# Sheet1.net
KiCad netlist of a schematic drawn in Altium Designer
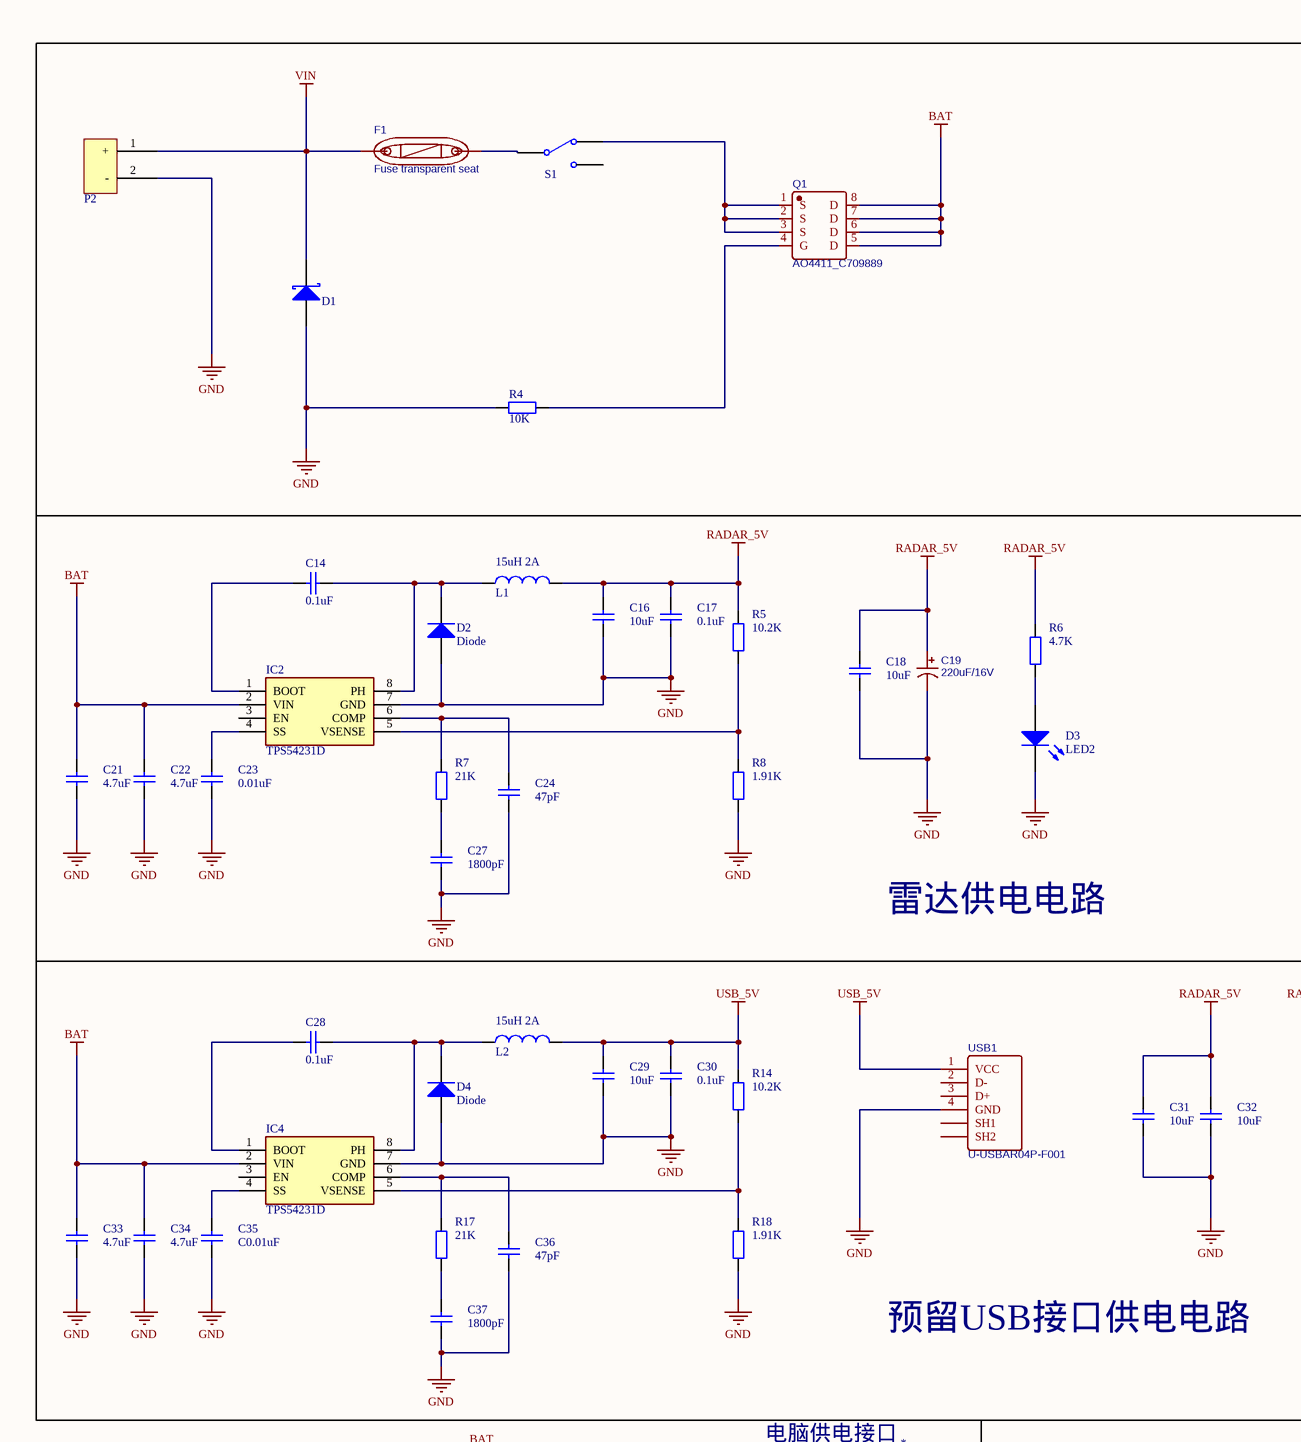
[diagram p0: Sheet1.SchDoc, top left]
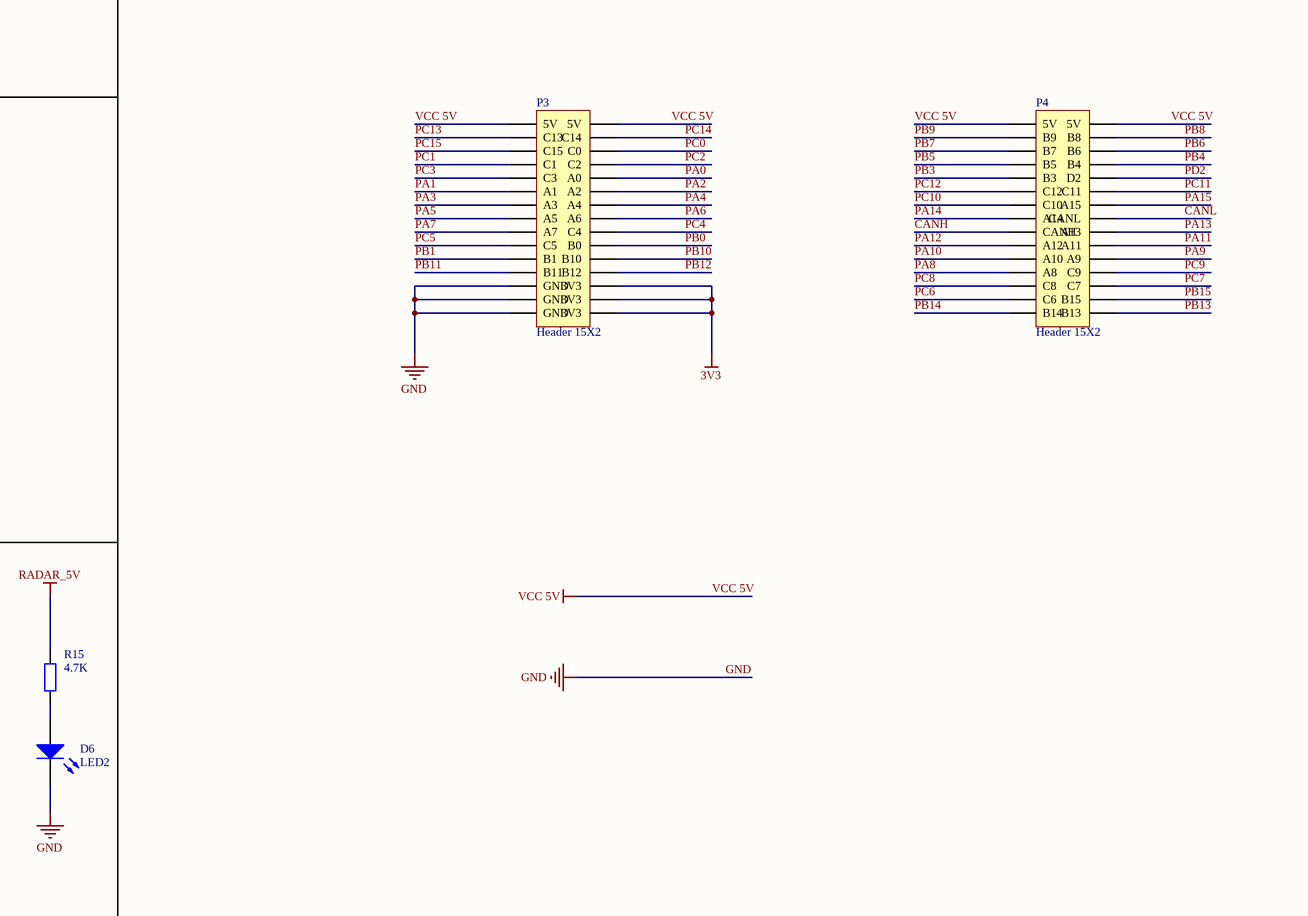
[diagram p1: Sheet1.SchDoc, top middle]
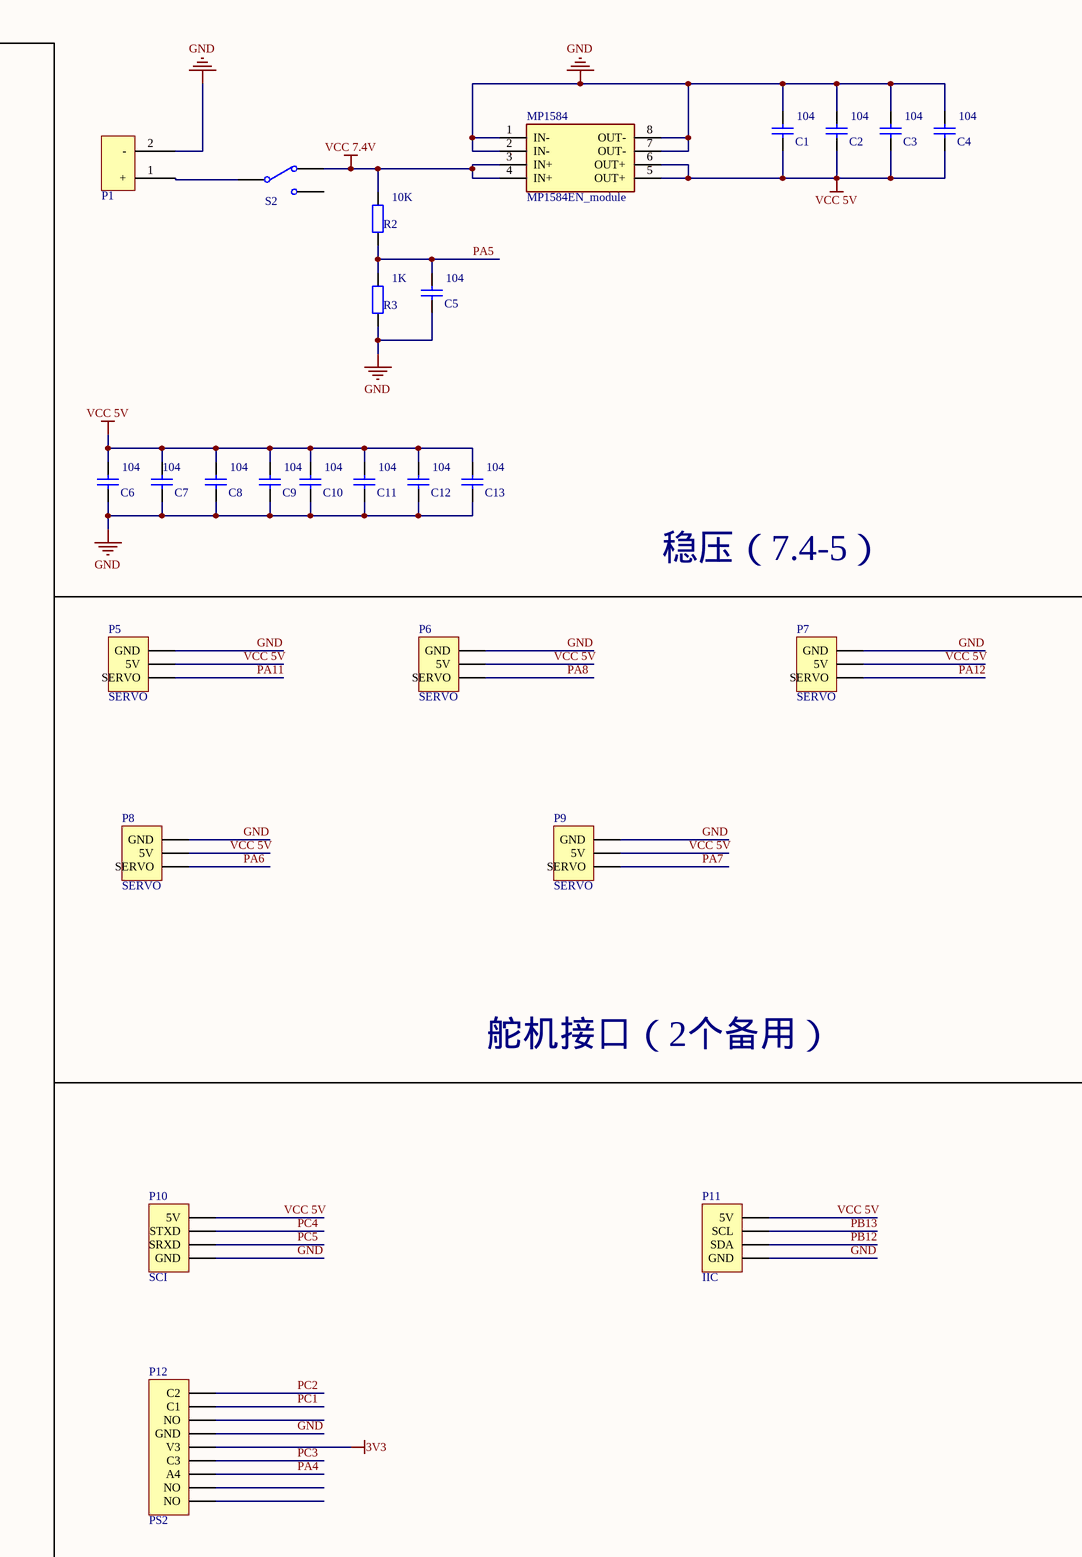
[diagram p2: Sheet1.SchDoc, top right]
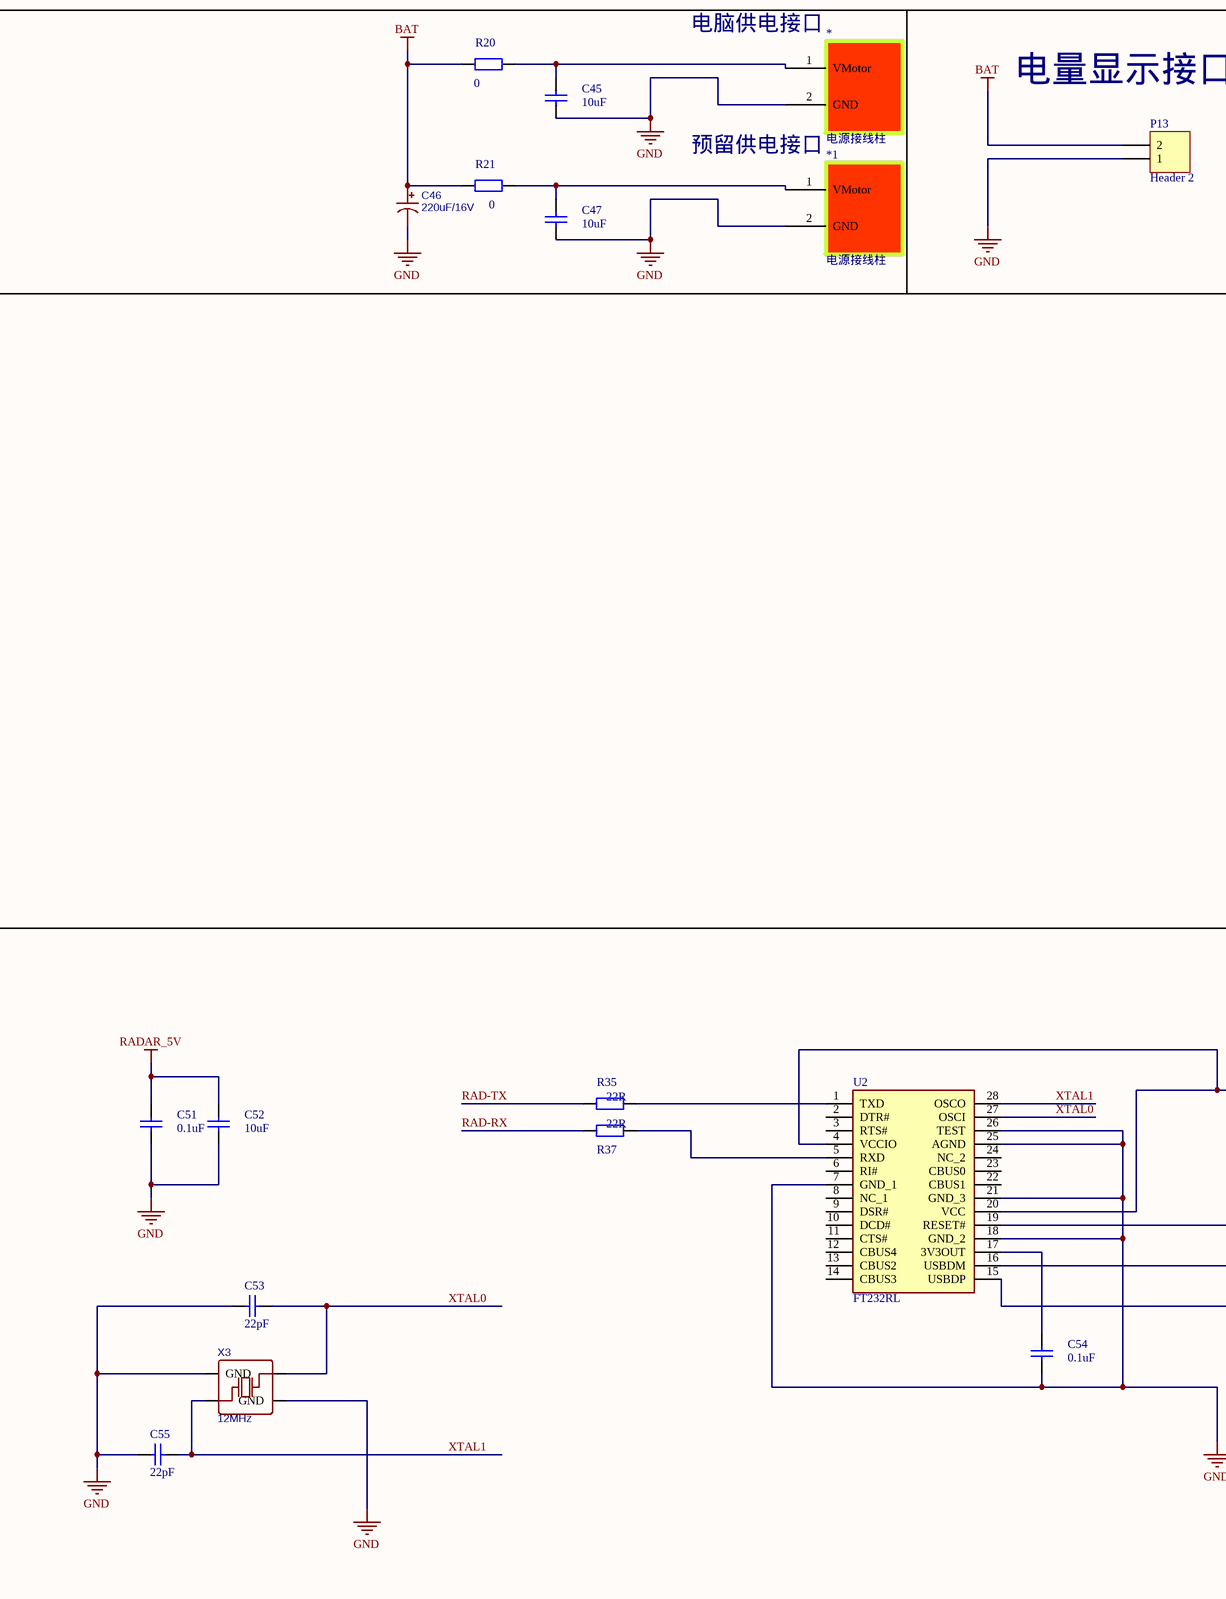
[diagram p3: Sheet1.SchDoc, bottom left]
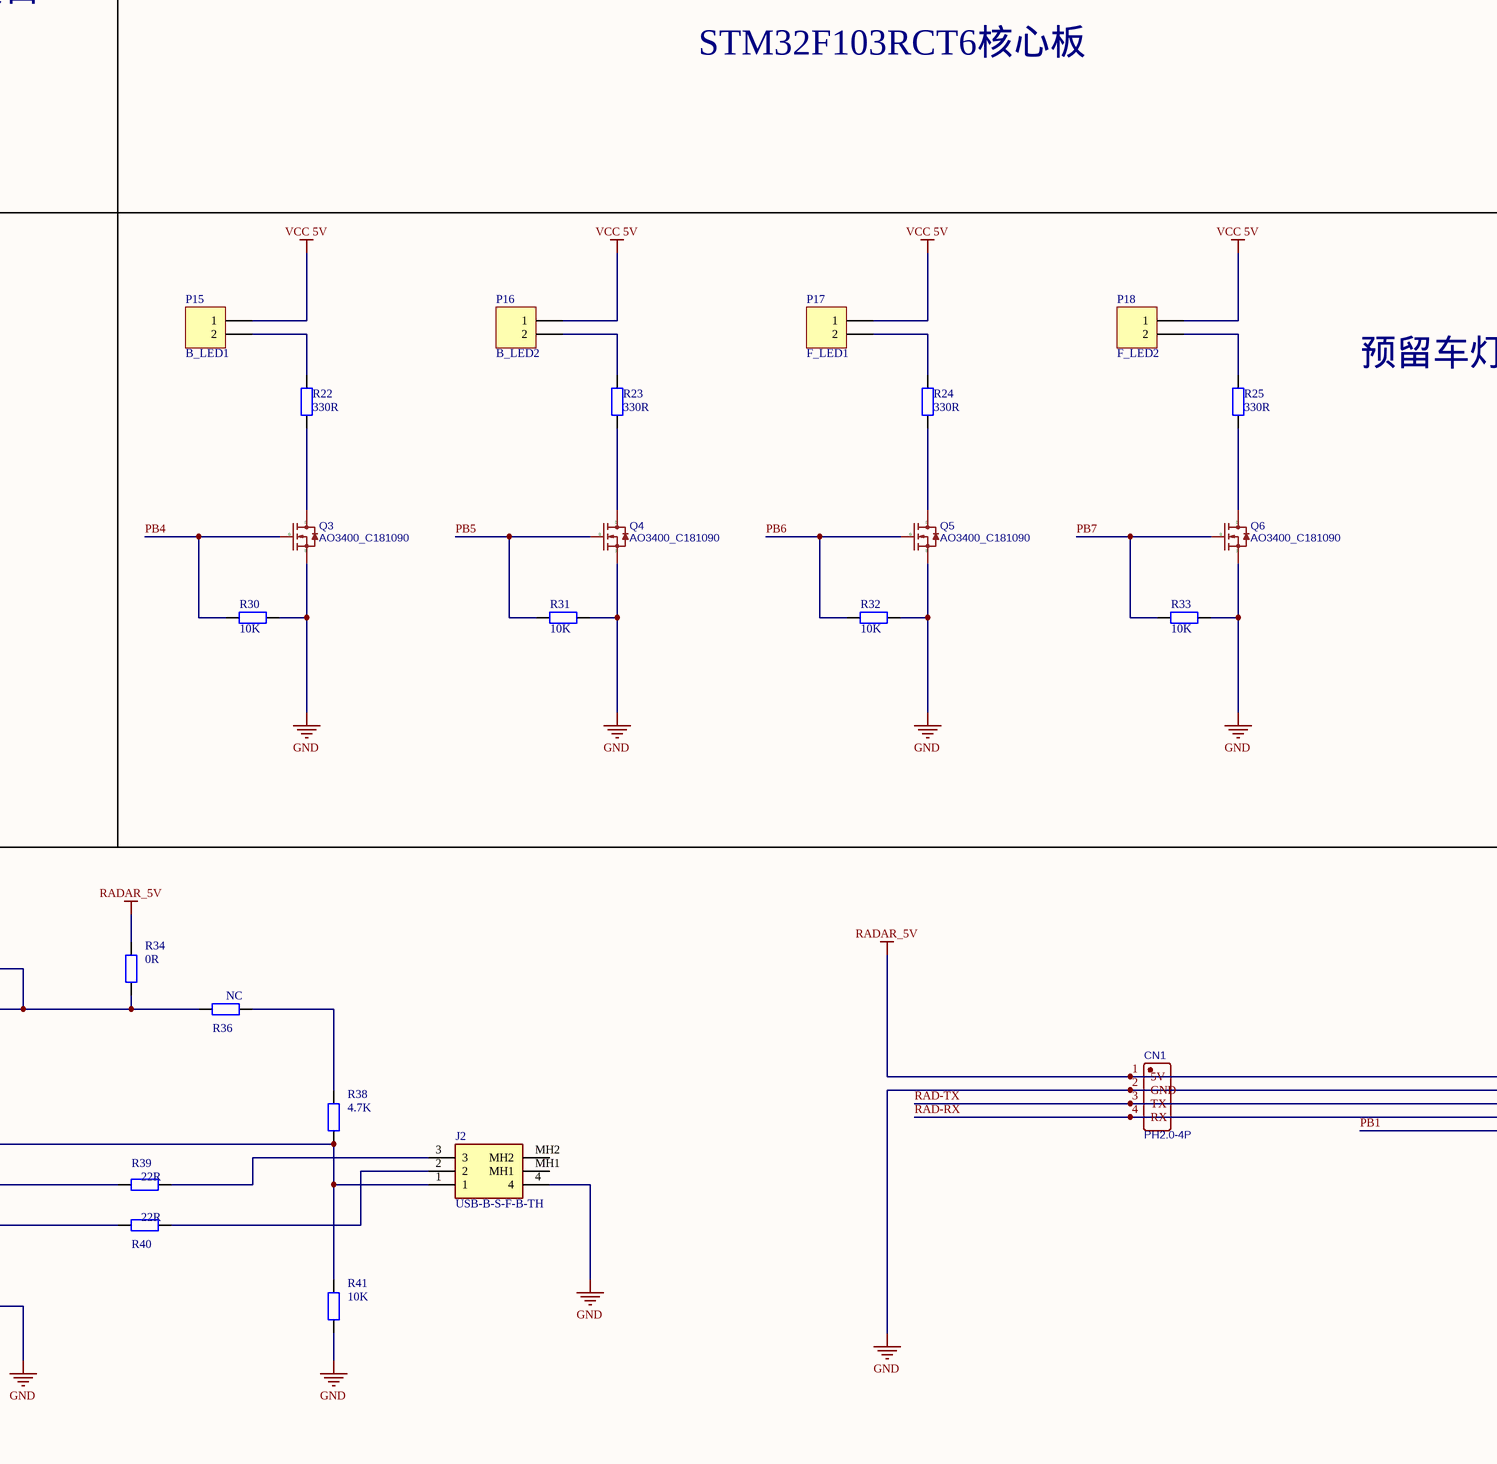
[diagram p4: Sheet1.SchDoc, bottom middle]
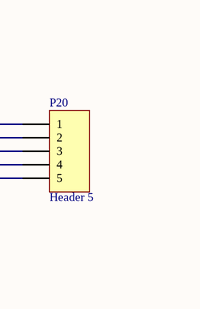
[diagram p5: Sheet1.SchDoc, bottom right]

(export (version "E")
  (design (tool "Eeschema 10.0.6"))
  (components
    (comp (ref "*") (value "电源接线柱") (footprint "接线柱") (libsource (lib "智能车元件") (part "电源接线柱")))
    (comp (ref "*1") (value "电源接线柱") (footprint "接线柱") (libsource (lib "智能车元件") (part "电源接线柱")))
    (comp (ref "C1")
      (value "104")
      (footprint "0805")
      (fields (field (name "PUBLISHER") "Altium Limited"))
      (libsource (lib "智能车元件") (part "C"))
    )
    (comp (ref "C2")
      (value "104")
      (footprint "0805")
      (fields (field (name "PUBLISHER") "Altium Limited"))
      (libsource (lib "智能车元件") (part "C"))
    )
    (comp (ref "C3")
      (value "104")
      (footprint "0805")
      (fields (field (name "PUBLISHER") "Altium Limited"))
      (libsource (lib "智能车元件") (part "C"))
    )
    (comp (ref "C4")
      (value "104")
      (footprint "0805")
      (fields (field (name "PUBLISHER") "Altium Limited"))
      (libsource (lib "智能车元件") (part "C"))
    )
    (comp (ref "C5")
      (value "104")
      (footprint "0805")
      (fields (field (name "PUBLISHER") "Altium Limited"))
      (libsource (lib "智能车元件") (part "C"))
    )
    (comp (ref "C6")
      (value "104")
      (footprint "0805")
      (fields (field (name "PUBLISHER") "Altium Limited"))
      (libsource (lib "智能车元件") (part "C"))
    )
    (comp (ref "C7")
      (value "104")
      (footprint "0805")
      (fields (field (name "PUBLISHER") "Altium Limited"))
      (libsource (lib "智能车元件") (part "C"))
    )
    (comp (ref "C8")
      (value "104")
      (footprint "0805")
      (fields (field (name "PUBLISHER") "Altium Limited"))
      (libsource (lib "智能车元件") (part "C"))
    )
    (comp (ref "C9")
      (value "104")
      (footprint "0805")
      (fields (field (name "PUBLISHER") "Altium Limited"))
      (libsource (lib "智能车元件") (part "C"))
    )
    (comp (ref "C10")
      (value "104")
      (footprint "0805")
      (fields (field (name "PUBLISHER") "Altium Limited"))
      (libsource (lib "智能车元件") (part "C"))
    )
    (comp (ref "C11")
      (value "104")
      (footprint "0805")
      (fields (field (name "PUBLISHER") "Altium Limited"))
      (libsource (lib "智能车元件") (part "C"))
    )
    (comp (ref "C12")
      (value "104")
      (footprint "0805")
      (fields (field (name "PUBLISHER") "Altium Limited"))
      (libsource (lib "智能车元件") (part "C"))
    )
    (comp (ref "C13")
      (value "104")
      (footprint "0805")
      (fields (field (name "PUBLISHER") "Altium Limited"))
      (libsource (lib "智能车元件") (part "C"))
    )
    (comp (ref "C14")
      (value "0.1uF")
      (footprint "0805")
      (fields (field (name "PUBLISHER") "Altium Limited"))
      (libsource (lib "智能车元件") (part "C"))
    )
    (comp (ref "C16")
      (value "10uF")
      (footprint "0805")
      (fields (field (name "PUBLISHER") "Altium Limited"))
      (libsource (lib "智能车元件") (part "C"))
    )
    (comp (ref "C17")
      (value "0.1uF")
      (footprint "0805")
      (fields (field (name "PUBLISHER") "Altium Limited"))
      (libsource (lib "智能车元件") (part "C"))
    )
    (comp (ref "C18")
      (value "10uF")
      (footprint "0805")
      (fields (field (name "PUBLISHER") "Altium Limited"))
      (libsource (lib "智能车元件") (part "C"))
    )
    (comp (ref "C19")
      (value "220uF/16V")
      (footprint "CAP-SMD_BD6.3-L6.6-W6.6-RD")
      (fields
        (field (name "BOM_MANUFACTURER PART") "ZV100M050E055R")
        (field (name "BOM_SUPPLIER PART") "C65228")
      )
      (libsource (lib "CAP_SMD") (part "10uF"))
    )
    (comp (ref "C21")
      (value "4.7uF")
      (footprint "0805")
      (fields (field (name "PUBLISHER") "Altium Limited"))
      (libsource (lib "智能车元件") (part "C"))
    )
    (comp (ref "C22")
      (value "4.7uF")
      (footprint "0805")
      (fields (field (name "PUBLISHER") "Altium Limited"))
      (libsource (lib "智能车元件") (part "C"))
    )
    (comp (ref "C23")
      (value "0.01uF")
      (footprint "0805")
      (fields (field (name "PUBLISHER") "Altium Limited"))
      (libsource (lib "智能车元件") (part "C"))
    )
    (comp (ref "C24")
      (value "47pF")
      (footprint "0805")
      (fields (field (name "PUBLISHER") "Altium Limited"))
      (libsource (lib "智能车元件") (part "C"))
    )
    (comp (ref "C27")
      (value "1800pF")
      (footprint "0805")
      (fields (field (name "PUBLISHER") "Altium Limited"))
      (libsource (lib "智能车元件") (part "C"))
    )
    (comp (ref "C28")
      (value "0.1uF")
      (footprint "0805")
      (fields (field (name "PUBLISHER") "Altium Limited"))
      (libsource (lib "智能车元件") (part "C"))
    )
    (comp (ref "C29")
      (value "10uF")
      (footprint "0805")
      (fields (field (name "PUBLISHER") "Altium Limited"))
      (libsource (lib "智能车元件") (part "C"))
    )
    (comp (ref "C30")
      (value "0.1uF")
      (footprint "0805")
      (fields (field (name "PUBLISHER") "Altium Limited"))
      (libsource (lib "智能车元件") (part "C"))
    )
    (comp (ref "C31")
      (value "10uF")
      (footprint "0805")
      (fields (field (name "PUBLISHER") "Altium Limited"))
      (libsource (lib "智能车元件") (part "C"))
    )
    (comp (ref "C32")
      (value "10uF")
      (footprint "0805")
      (fields (field (name "PUBLISHER") "Altium Limited"))
      (libsource (lib "智能车元件") (part "C"))
    )
    (comp (ref "C33")
      (value "4.7uF")
      (footprint "0805")
      (fields (field (name "PUBLISHER") "Altium Limited"))
      (libsource (lib "智能车元件") (part "C"))
    )
    (comp (ref "C34")
      (value "4.7uF")
      (footprint "0805")
      (fields (field (name "PUBLISHER") "Altium Limited"))
      (libsource (lib "智能车元件") (part "C"))
    )
    (comp (ref "C35")
      (value "C0.01uF")
      (footprint "0805")
      (fields (field (name "PUBLISHER") "Altium Limited"))
      (libsource (lib "智能车元件") (part "C"))
    )
    (comp (ref "C36")
      (value "47pF")
      (footprint "0805")
      (fields (field (name "PUBLISHER") "Altium Limited"))
      (libsource (lib "智能车元件") (part "C"))
    )
    (comp (ref "C37")
      (value "1800pF")
      (footprint "0805")
      (fields (field (name "PUBLISHER") "Altium Limited"))
      (libsource (lib "智能车元件") (part "C"))
    )
    (comp (ref "C45")
      (value "10uF")
      (footprint "0805")
      (fields (field (name "PUBLISHER") "Altium Limited"))
      (libsource (lib "智能车元件") (part "C"))
    )
    (comp (ref "C46")
      (value "220uF/16V")
      (footprint "CAP-SMD_BD6.3-L6.6-W6.6-RD")
      (fields
        (field (name "BOM_MANUFACTURER PART") "ZV100M050E055R")
        (field (name "BOM_SUPPLIER PART") "C65228")
      )
      (libsource (lib "CAP_SMD") (part "10uF"))
    )
    (comp (ref "C47")
      (value "10uF")
      (footprint "0805")
      (fields (field (name "PUBLISHER") "Altium Limited"))
      (libsource (lib "智能车元件") (part "C"))
    )
    (comp (ref "C51")
      (value "0.1uF")
      (footprint "0805")
      (fields (field (name "PUBLISHER") "Altium Limited"))
      (libsource (lib "智能车元件") (part "C"))
    )
    (comp (ref "C52")
      (value "10uF")
      (footprint "0805")
      (fields (field (name "PUBLISHER") "Altium Limited"))
      (libsource (lib "智能车元件") (part "C"))
    )
    (comp (ref "C53")
      (value "22pF")
      (footprint "0805")
      (fields (field (name "PUBLISHER") "Altium Limited"))
      (libsource (lib "智能车元件") (part "C"))
    )
    (comp (ref "C54")
      (value "0.1uF")
      (footprint "0805")
      (fields (field (name "PUBLISHER") "Altium Limited"))
      (libsource (lib "智能车元件") (part "C"))
    )
    (comp (ref "C55")
      (value "22pF")
      (footprint "0805")
      (fields (field (name "PUBLISHER") "Altium Limited"))
      (libsource (lib "智能车元件") (part "C"))
    )
    (comp (ref "CN1")
      (value "PH2.0-4P")
      (footprint "CONN-TH_PH2.0-4P")
      (fields (field (name "BOM_SUPPLIER PART") "C722763") (field (name "CONTRIBUTOR") "LCSC"))
      (libsource (lib "4P-2.0") (part "PH2.0-4P"))
    )
    (comp (ref "D1") (value "D-SS12") (footprint "SMA") (libsource (lib "智能车元件") (part "D-SS12")))
    (comp (ref "D2")
      (value "Diode")
      (footprint "SMC")
      (description "Default Diode")
      (fields (field (name "PUBLISHER") "Altium Limited"))
      (libsource (lib "Miscellaneous Devices") (part "Diode"))
    )
    (comp (ref "D3")
      (value "LED2")
      (footprint "3.2X1.6X1.1")
      (description "Typical RED, GREEN, YELLOW, AMBER GaAs LED")
      (fields (field (name "PUBLISHER") "Altium Limited"))
      (libsource (lib "Miscellaneous Devices") (part "LED2"))
    )
    (comp (ref "D4")
      (value "Diode")
      (footprint "SMC")
      (description "Default Diode")
      (fields (field (name "PUBLISHER") "Altium Limited"))
      (libsource (lib "Miscellaneous Devices") (part "Diode"))
    )
    (comp (ref "D6")
      (value "LED2")
      (footprint "3.2X1.6X1.1")
      (description "Typical RED, GREEN, YELLOW, AMBER GaAs LED")
      (fields (field (name "PUBLISHER") "Altium Limited"))
      (libsource (lib "Miscellaneous Devices") (part "LED2"))
    )
    (comp (ref "F1")
      (value "Fuse transparent seat")
      (footprint "FUSE-TH_L24.5-W9.8-P22.5")
      (fields (field (name "BOM_SUPPLIER PART") "C58066"))
      (libsource (lib "FUSE seat") (part "Fuse transparent seat"))
    )
    (comp (ref "IC2")
      (value "TPS54231D")
      (footprint "CAR1:SOIC127P600X175-8N")
      (description "Integrated Circuit")
      (fields (field (name "MOUSER PART NUMBER") "595-TPS54231D"))
      (libsource (lib "CAR1") (part "TPS54231D"))
    )
    (comp (ref "IC4")
      (value "TPS54231D")
      (footprint "CAR1:SOIC127P600X175-8N")
      (description "Integrated Circuit")
      (fields (field (name "MOUSER PART NUMBER") "595-TPS54231D"))
      (libsource (lib "CAR1") (part "TPS54231D"))
    )
    (comp (ref "J2")
      (value "USB-B-S-F-B-TH")
      (footprint "CAR1:USBBSFBTH")
      (description "Connector")
      (fields (field (name "MOUSER PART NUMBER") "200-USBBSFBTH"))
      (libsource (lib "CAR1") (part "USB-B-S-F-B-TH"))
    )
    (comp (ref "L1") (value "15uH 2A") (footprint "L-7*7") (libsource (lib "智能车元件") (part "L")))
    (comp (ref "L2") (value "15uH 2A") (footprint "L-7*7") (libsource (lib "智能车元件") (part "L")))
    (comp (ref "MP1584")
      (value "MP1584EN_module")
      (footprint "MP1584EN_module")
      (libsource (lib "CAR1") (part "MP1584EN_module"))
    )
    (comp (ref "P1") (value "P") (footprint "T插1") (libsource (lib "智能车元件") (part "CON-T插")))
    (comp (ref "P2") (value "P") (footprint "T插1") (libsource (lib "") (part "CON-T插_1")))
    (comp (ref "P3")
      (value "Header 15X2")
      (footprint "HDR2X15")
      (description "Header, 15-Pin, Dual row")
      (fields (field (name "PUBLISHER") "Altium Limited"))
      (libsource (lib "Miscellaneous Connectors") (part "Header 15X2"))
    )
    (comp (ref "P4")
      (value "Header 15X2")
      (footprint "HDR2X15")
      (description "Header, 15-Pin, Dual row")
      (fields (field (name "PUBLISHER") "Altium Limited"))
      (libsource (lib "Miscellaneous Connectors") (part "Header 15X2"))
    )
    (comp (ref "P5")
      (value "SERVO")
      (footprint "HDR1X3")
      (description "Header, 3-Pin")
      (fields (field (name "PUBLISHER") "Altium Limited"))
      (libsource (lib "Miscellaneous Connectors") (part "Header 3"))
    )
    (comp (ref "P6")
      (value "SERVO")
      (footprint "HDR1X3")
      (description "Header, 3-Pin")
      (fields (field (name "PUBLISHER") "Altium Limited"))
      (libsource (lib "Miscellaneous Connectors") (part "Header 3"))
    )
    (comp (ref "P7")
      (value "SERVO")
      (footprint "HDR1X3")
      (description "Header, 3-Pin")
      (fields (field (name "PUBLISHER") "Altium Limited"))
      (libsource (lib "Miscellaneous Connectors") (part "Header 3"))
    )
    (comp (ref "P8")
      (value "SERVO")
      (footprint "HDR1X3")
      (description "Header, 3-Pin")
      (fields (field (name "PUBLISHER") "Altium Limited"))
      (libsource (lib "Miscellaneous Connectors") (part "Header 3"))
    )
    (comp (ref "P9")
      (value "SERVO")
      (footprint "HDR1X3")
      (description "Header, 3-Pin")
      (fields (field (name "PUBLISHER") "Altium Limited"))
      (libsource (lib "Miscellaneous Connectors") (part "Header 3"))
    )
    (comp (ref "P10")
      (value "SCI")
      (footprint "HDR1X4")
      (description "Header, 4-Pin")
      (fields (field (name "PUBLISHER") "Altium Limited"))
      (libsource (lib "Miscellaneous Connectors") (part "Header 4"))
    )
    (comp (ref "P11")
      (value "IIC")
      (footprint "HDR1X4")
      (description "Header, 4-Pin")
      (fields (field (name "PUBLISHER") "Altium Limited"))
      (libsource (lib "Miscellaneous Connectors") (part "Header 4"))
    )
    (comp (ref "P12")
      (value "PS2")
      (footprint "HDR1X9")
      (description "Header, 9-Pin")
      (fields (field (name "PUBLISHER") "Altium Limited"))
      (libsource (lib "Miscellaneous Connectors") (part "Header 9"))
    )
    (comp (ref "P13")
      (value "Header 2")
      (footprint "HDR1X2")
      (description "Header, 2-Pin")
      (fields (field (name "PUBLISHER") "Altium Limited"))
      (libsource (lib "") (part "Header 2_1"))
    )
    (comp (ref "P15")
      (value "B_LED1")
      (footprint "HDR1X2")
      (description "Header, 2-Pin")
      (fields (field (name "PUBLISHER") "Altium Limited"))
      (libsource (lib "Miscellaneous Connectors") (part "Header 2"))
    )
    (comp (ref "P16")
      (value "B_LED2")
      (footprint "HDR1X2")
      (description "Header, 2-Pin")
      (fields (field (name "PUBLISHER") "Altium Limited"))
      (libsource (lib "Miscellaneous Connectors") (part "Header 2"))
    )
    (comp (ref "P17")
      (value "F_LED1")
      (footprint "HDR1X2")
      (description "Header, 2-Pin")
      (fields (field (name "PUBLISHER") "Altium Limited"))
      (libsource (lib "Miscellaneous Connectors") (part "Header 2"))
    )
    (comp (ref "P18")
      (value "F_LED2")
      (footprint "HDR1X2")
      (description "Header, 2-Pin")
      (fields (field (name "PUBLISHER") "Altium Limited"))
      (libsource (lib "Miscellaneous Connectors") (part "Header 2"))
    )
    (comp (ref "P20")
      (value "Header 5")
      (footprint "HDR1X5")
      (description "Header, 5-Pin")
      (fields (field (name "PUBLISHER") "Altium Limited"))
      (libsource (lib "Miscellaneous Connectors") (part "Header 5"))
    )
    (comp (ref "Q1")
      (value "AO4411_C709889")
      (footprint "SO-8_L4.9-W3.9-P1.27-LS5.9-BL")
      (fields
        (field (name "BOM_SUPPLIER PART") "C709889")
        (field (name "BOM_MANUFACTURER PART") "AO4411")
        (field (name "CONTRIBUTOR") "LCSC")
      )
      (libsource (lib "AO4411") (part "AO4411_C709889"))
    )
    (comp (ref "Q3")
      (value "AO3400_C181090")
      (footprint "SOT-23-3_L2.9-W1.3-P1.90-LS2.4-BR")
      (fields
        (field (name "BOM_MANUFACTURER PART") "AO3400")
        (field (name "BOM_SUPPLIER PART") "C181090")
        (field (name "CONTRIBUTOR") "LCSC")
      )
      (libsource (lib "Free Documents") (part "AO3400_C181090"))
    )
    (comp (ref "Q4")
      (value "AO3400_C181090")
      (footprint "SOT-23-3_L2.9-W1.3-P1.90-LS2.4-BR")
      (fields
        (field (name "BOM_MANUFACTURER PART") "AO3400")
        (field (name "BOM_SUPPLIER PART") "C181090")
        (field (name "CONTRIBUTOR") "LCSC")
      )
      (libsource (lib "Free Documents") (part "AO3400_C181090"))
    )
    (comp (ref "Q5")
      (value "AO3400_C181090")
      (footprint "SOT-23-3_L2.9-W1.3-P1.90-LS2.4-BR")
      (fields
        (field (name "BOM_MANUFACTURER PART") "AO3400")
        (field (name "BOM_SUPPLIER PART") "C181090")
        (field (name "CONTRIBUTOR") "LCSC")
      )
      (libsource (lib "Free Documents") (part "AO3400_C181090"))
    )
    (comp (ref "Q6")
      (value "AO3400_C181090")
      (footprint "SOT-23-3_L2.9-W1.3-P1.90-LS2.4-BR")
      (fields
        (field (name "BOM_MANUFACTURER PART") "AO3400")
        (field (name "BOM_SUPPLIER PART") "C181090")
        (field (name "CONTRIBUTOR") "LCSC")
      )
      (libsource (lib "Free Documents") (part "AO3400_C181090"))
    )
    (comp (ref "R2") (value "10K") (footprint "0805") (libsource (lib "") (part "R_2")))
    (comp (ref "R3") (value "1K") (footprint "0805") (libsource (lib "") (part "R_2")))
    (comp (ref "R4") (value "10K") (footprint "0805") (libsource (lib "") (part "R_3")))
    (comp (ref "R5") (value "10.2K") (footprint "0805") (libsource (lib "") (part "R_2")))
    (comp (ref "R6") (value "4.7K") (footprint "0805") (libsource (lib "") (part "R_2")))
    (comp (ref "R7") (value "21K") (footprint "0805") (libsource (lib "") (part "R_2")))
    (comp (ref "R8") (value "1.91K") (footprint "0805") (libsource (lib "") (part "R_2")))
    (comp (ref "R14") (value "10.2K") (footprint "0805") (libsource (lib "") (part "R_2")))
    (comp (ref "R15") (value "4.7K") (footprint "0805") (libsource (lib "") (part "R_2")))
    (comp (ref "R17") (value "21K") (footprint "0805") (libsource (lib "") (part "R_2")))
    (comp (ref "R18") (value "1.91K") (footprint "0805") (libsource (lib "") (part "R_2")))
    (comp (ref "R20") (value "0") (footprint "0805") (libsource (lib "") (part "R_1")))
    (comp (ref "R21") (value "0") (footprint "0805") (libsource (lib "") (part "R_1")))
    (comp (ref "R22") (value "330R") (footprint "0805") (libsource (lib "智能车元件") (part "R")))
    (comp (ref "R23") (value "330R") (footprint "0805") (libsource (lib "智能车元件") (part "R")))
    (comp (ref "R24") (value "330R") (footprint "0805") (libsource (lib "智能车元件") (part "R")))
    (comp (ref "R25") (value "330R") (footprint "0805") (libsource (lib "智能车元件") (part "R")))
    (comp (ref "R30") (value "10K") (footprint "0805") (libsource (lib "") (part "R_1")))
    (comp (ref "R31") (value "10K") (footprint "0805") (libsource (lib "") (part "R_1")))
    (comp (ref "R32") (value "10K") (footprint "0805") (libsource (lib "") (part "R_1")))
    (comp (ref "R33") (value "10K") (footprint "0805") (libsource (lib "") (part "R_1")))
    (comp (ref "R34") (value "0R") (footprint "0805") (libsource (lib "") (part "R_2")))
    (comp (ref "R35") (value "22R") (footprint "0805") (libsource (lib "") (part "R_1")))
    (comp (ref "R36") (value "NC") (footprint "0805") (libsource (lib "") (part "R_1")))
    (comp (ref "R37") (value "22R") (footprint "0805") (libsource (lib "") (part "R_1")))
    (comp (ref "R38") (value "4.7K") (footprint "0805") (libsource (lib "") (part "R_2")))
    (comp (ref "R39") (value "22R") (footprint "0805") (libsource (lib "") (part "R_1")))
    (comp (ref "R40") (value "22R") (footprint "0805") (libsource (lib "") (part "R_1")))
    (comp (ref "R41") (value "10K") (footprint "0805") (libsource (lib "") (part "R_2")))
    (comp (ref "S1") (value "SWITCH") (footprint "纽子开关") (libsource (lib "智能车元件") (part "SW-钮子开关")))
    (comp (ref "S2") (value "SWITCH") (footprint "纽子开关") (libsource (lib "智能车元件") (part "SW-钮子开关")))
    (comp (ref "U2")
      (value "FT232RL")
      (footprint "CAR1:SOP65P778X200-28N")
      (description "Integrated Circuit")
      (libsource (lib "CAR1") (part "FT232RL"))
    )
    (comp (ref "USB1")
      (value "U-USBAR04P-F001")
      (footprint "USB-A-TH_USB-302-T")
      (fields (field (name "BOM_SUPPLIER PART") "C386736") (field (name "CONTRIBUTOR") "LCSC"))
      (libsource (lib "USB-A") (part "U-USBAR04P-F001"))
    )
    (comp (ref "X3")
      (value "12MHz")
      (footprint "OSC-SMD_4P-L3.2-W2.5-BL")
      (fields
        (field (name "BOM_SUPPLIER PART") "C258939")
        (field (name "BOM_MANUFACTURER PART") "M12000J134")
        (field (name "CONTRIBUTOR") "LCSC")
      )
      (libsource (lib "Free Documents") (part "12MHz"))
    )
  )
  (nets
    (net (code "1") (name "/CANH") (class "Default")
      (node (ref "P4") (pin "17") (pinfunction "CANH_17") (pintype "passive"))
    )
    (net (code "2") (name "/CANL") (class "Default")
      (node (ref "P4") (pin "16") (pinfunction "CANL_16") (pintype "passive"))
    )
    (net (code "3") (name "/PA0") (class "Default")
      (node (ref "P3") (pin "10") (pinfunction "D2_10") (pintype "passive"))
    )
    (net (code "4") (name "/PA1") (class "Default")
      (node (ref "P3") (pin "11") (pinfunction "C12_11") (pintype "passive"))
    )
    (net (code "5") (name "/PA2") (class "Default")
      (node (ref "P3") (pin "12") (pinfunction "C11_12") (pintype "passive"))
    )
    (net (code "6") (name "/PA3") (class "Default")
      (node (ref "P3") (pin "13") (pinfunction "C10_13") (pintype "passive"))
    )
    (net (code "7") (name "/PA4") (class "Default")
      (node (ref "P12") (pin "7") (pinfunction "A4_7") (pintype "passive"))
      (node (ref "P3") (pin "14") (pinfunction "A15_14") (pintype "passive"))
    )
    (net (code "8") (name "/PA5") (class "Default")
      (node (ref "C5") (pin "2") (pinfunction "2_2") (pintype "passive"))
      (node (ref "P3") (pin "15") (pinfunction "A14_15") (pintype "passive"))
      (node (ref "R2") (pin "1") (pinfunction "1_1") (pintype "passive"))
      (node (ref "R3") (pin "2") (pinfunction "2_2") (pintype "passive"))
    )
    (net (code "9") (name "/PA6") (class "Default")
      (node (ref "P3") (pin "16") (pinfunction "CANL_16") (pintype "passive"))
      (node (ref "P8") (pin "3") (pinfunction "SERVO_3") (pintype "passive"))
    )
    (net (code "10") (name "/PA7") (class "Default")
      (node (ref "P3") (pin "17") (pinfunction "CANH_17") (pintype "passive"))
      (node (ref "P9") (pin "3") (pinfunction "SERVO_3") (pintype "passive"))
    )
    (net (code "11") (name "/PA8") (class "Default")
      (node (ref "P4") (pin "23") (pinfunction "A8_23") (pintype "passive"))
      (node (ref "P6") (pin "3") (pinfunction "SERVO_3") (pintype "passive"))
    )
    (net (code "12") (name "/PA9") (class "Default")
      (node (ref "P4") (pin "22") (pinfunction "A9_22") (pintype "passive"))
    )
    (net (code "13") (name "/PA10") (class "Default")
      (node (ref "P4") (pin "21") (pinfunction "A10_21") (pintype "passive"))
    )
    (net (code "14") (name "/PA11") (class "Default")
      (node (ref "P4") (pin "20") (pinfunction "A11_20") (pintype "passive"))
      (node (ref "P5") (pin "3") (pinfunction "SERVO_3") (pintype "passive"))
    )
    (net (code "15") (name "/PA12") (class "Default")
      (node (ref "P4") (pin "19") (pinfunction "A12_19") (pintype "passive"))
      (node (ref "P7") (pin "3") (pinfunction "SERVO_3") (pintype "passive"))
    )
    (net (code "16") (name "/PA13") (class "Default")
      (node (ref "P4") (pin "18") (pinfunction "A13_18") (pintype "passive"))
    )
    (net (code "17") (name "/PA14") (class "Default")
      (node (ref "P4") (pin "15") (pinfunction "A14_15") (pintype "passive"))
    )
    (net (code "18") (name "/PA15") (class "Default")
      (node (ref "P4") (pin "14") (pinfunction "A15_14") (pintype "passive"))
    )
    (net (code "19") (name "/PB0") (class "Default")
      (node (ref "P3") (pin "20") (pinfunction "A11_20") (pintype "passive"))
    )
    (net (code "20") (name "/PB1") (class "Default")
      (node (ref "P20") (pin "5") (pinfunction "5_5") (pintype "passive"))
      (node (ref "P3") (pin "21") (pinfunction "A10_21") (pintype "passive"))
    )
    (net (code "21") (name "/PB3") (class "Default")
      (node (ref "P4") (pin "9") (pinfunction "B3_9") (pintype "passive"))
    )
    (net (code "22") (name "/PB4") (class "Default")
      (node (ref "P4") (pin "8") (pinfunction "B4_8") (pintype "passive"))
      (node (ref "Q3") (pin "1") (pinfunction "G_1") (pintype "passive"))
      (node (ref "R30") (pin "1") (pinfunction "1_1") (pintype "passive"))
    )
    (net (code "23") (name "/PB5") (class "Default")
      (node (ref "P4") (pin "7") (pinfunction "B5_7") (pintype "passive"))
      (node (ref "Q4") (pin "1") (pinfunction "G_1") (pintype "passive"))
      (node (ref "R31") (pin "1") (pinfunction "1_1") (pintype "passive"))
    )
    (net (code "24") (name "/PB6") (class "Default")
      (node (ref "P4") (pin "6") (pinfunction "B6_6") (pintype "passive"))
      (node (ref "Q5") (pin "1") (pinfunction "G_1") (pintype "passive"))
      (node (ref "R32") (pin "1") (pinfunction "1_1") (pintype "passive"))
    )
    (net (code "25") (name "/PB7") (class "Default")
      (node (ref "P4") (pin "5") (pinfunction "B7_5") (pintype "passive"))
      (node (ref "Q6") (pin "1") (pinfunction "G_1") (pintype "passive"))
      (node (ref "R33") (pin "1") (pinfunction "1_1") (pintype "passive"))
    )
    (net (code "26") (name "/PB8") (class "Default")
      (node (ref "P4") (pin "4") (pinfunction "B8_4") (pintype "passive"))
    )
    (net (code "27") (name "/PB9") (class "Default")
      (node (ref "P4") (pin "3") (pinfunction "B9_3") (pintype "passive"))
    )
    (net (code "28") (name "/PB10") (class "Default")
      (node (ref "P3") (pin "22") (pinfunction "A9_22") (pintype "passive"))
    )
    (net (code "29") (name "/PB11") (class "Default")
      (node (ref "P3") (pin "23") (pinfunction "A8_23") (pintype "passive"))
    )
    (net (code "30") (name "/PB12") (class "Default")
      (node (ref "P11") (pin "3") (pinfunction "SDA_3") (pintype "passive"))
      (node (ref "P3") (pin "24") (pinfunction "C9_24") (pintype "passive"))
    )
    (net (code "31") (name "/PB13") (class "Default")
      (node (ref "P11") (pin "2") (pinfunction "SCL_2") (pintype "passive"))
      (node (ref "P4") (pin "30") (pinfunction "B13_30") (pintype "passive"))
    )
    (net (code "32") (name "/PB14") (class "Default")
      (node (ref "P4") (pin "29") (pinfunction "B14_29") (pintype "passive"))
    )
    (net (code "33") (name "/PB15") (class "Default")
      (node (ref "P4") (pin "28") (pinfunction "B15_28") (pintype "passive"))
    )
    (net (code "34") (name "/PC0") (class "Default")
      (node (ref "P3") (pin "6") (pinfunction "B6_6") (pintype "passive"))
    )
    (net (code "35") (name "/PC1") (class "Default")
      (node (ref "P12") (pin "2") (pinfunction "C1_2") (pintype "passive"))
      (node (ref "P3") (pin "7") (pinfunction "B5_7") (pintype "passive"))
    )
    (net (code "36") (name "/PC2") (class "Default")
      (node (ref "P12") (pin "1") (pinfunction "C2_1") (pintype "passive"))
      (node (ref "P3") (pin "8") (pinfunction "B4_8") (pintype "passive"))
    )
    (net (code "37") (name "/PC3") (class "Default")
      (node (ref "P12") (pin "6") (pinfunction "C3_6") (pintype "passive"))
      (node (ref "P3") (pin "9") (pinfunction "B3_9") (pintype "passive"))
    )
    (net (code "38") (name "/PC4") (class "Default")
      (node (ref "P10") (pin "2") (pinfunction "SCL_2") (pintype "passive"))
      (node (ref "P3") (pin "18") (pinfunction "A13_18") (pintype "passive"))
    )
    (net (code "39") (name "/PC5") (class "Default")
      (node (ref "P10") (pin "3") (pinfunction "SDA_3") (pintype "passive"))
      (node (ref "P3") (pin "19") (pinfunction "A12_19") (pintype "passive"))
    )
    (net (code "40") (name "/PC6") (class "Default")
      (node (ref "P4") (pin "27") (pinfunction "C6_27") (pintype "passive"))
    )
    (net (code "41") (name "/PC7") (class "Default")
      (node (ref "P4") (pin "26") (pinfunction "C7_26") (pintype "passive"))
    )
    (net (code "42") (name "/PC8") (class "Default")
      (node (ref "P4") (pin "25") (pinfunction "C8_25") (pintype "passive"))
    )
    (net (code "43") (name "/PC9") (class "Default")
      (node (ref "P4") (pin "24") (pinfunction "C9_24") (pintype "passive"))
    )
    (net (code "44") (name "/PC10") (class "Default")
      (node (ref "P4") (pin "13") (pinfunction "C10_13") (pintype "passive"))
    )
    (net (code "45") (name "/PC11") (class "Default")
      (node (ref "P4") (pin "12") (pinfunction "C11_12") (pintype "passive"))
    )
    (net (code "46") (name "/PC12") (class "Default")
      (node (ref "P4") (pin "11") (pinfunction "C12_11") (pintype "passive"))
    )
    (net (code "47") (name "/PC13") (class "Default")
      (node (ref "P3") (pin "3") (pinfunction "B9_3") (pintype "passive"))
    )
    (net (code "48") (name "/PC14") (class "Default")
      (node (ref "P3") (pin "4") (pinfunction "B8_4") (pintype "passive"))
    )
    (net (code "49") (name "/PC15") (class "Default")
      (node (ref "P3") (pin "5") (pinfunction "B7_5") (pintype "passive"))
    )
    (net (code "50") (name "/PD2") (class "Default")
      (node (ref "P4") (pin "10") (pinfunction "D2_10") (pintype "passive"))
    )
    (net (code "51") (name "/RAD-RX") (class "Default")
      (node (ref "CN1") (pin "4") (pinfunction "RX_4") (pintype "passive"))
      (node (ref "P20") (pin "4") (pinfunction "4_4") (pintype "passive"))
      (node (ref "R37") (pin "1") (pinfunction "1_1") (pintype "passive"))
    )
    (net (code "52") (name "/RAD-TX") (class "Default")
      (node (ref "CN1") (pin "3") (pinfunction "TX_3") (pintype "passive"))
      (node (ref "P20") (pin "3") (pinfunction "3_3") (pintype "passive"))
      (node (ref "R35") (pin "1") (pinfunction "1_1") (pintype "passive"))
    )
    (net (code "53") (name "/XTAL0") (class "Default")
      (node (ref "C53") (pin "1") (pinfunction "1_1") (pintype "passive"))
      (node (ref "U2") (pin "27") (pinfunction "OSCI_27") (pintype "passive"))
      (node (ref "X3") (pin "3") (pinfunction "OSC2_3") (pintype "passive"))
    )
    (net (code "54") (name "/XTAL1") (class "Default")
      (node (ref "C55") (pin "1") (pinfunction "1_1") (pintype "passive"))
      (node (ref "U2") (pin "28") (pinfunction "OSCO_28") (pintype "passive"))
      (node (ref "X3") (pin "1") (pinfunction "OSC1_1") (pintype "passive"))
    )
    (net (code "55") (name "3V3") (class "Default")
      (node (ref "P12") (pin "5") (pinfunction "V3_5") (pintype "passive"))
      (node (ref "P3") (pin "26") (pinfunction "C7_26") (pintype "passive"))
      (node (ref "P3") (pin "28") (pinfunction "B15_28") (pintype "passive"))
      (node (ref "P3") (pin "30") (pinfunction "B13_30") (pintype "passive"))
    )
    (net (code "56") (name "BAT") (class "Default")
      (node (ref "C21") (pin "2") (pinfunction "2_2") (pintype "passive"))
      (node (ref "C22") (pin "2") (pinfunction "2_2") (pintype "passive"))
      (node (ref "C33") (pin "2") (pinfunction "2_2") (pintype "passive"))
      (node (ref "C34") (pin "2") (pinfunction "2_2") (pintype "passive"))
      (node (ref "C46") (pin "1") (pinfunction "1_1") (pintype "passive"))
      (node (ref "IC2") (pin "2") (pinfunction "VIN_2") (pintype "passive"))
      (node (ref "IC4") (pin "2") (pinfunction "VIN_2") (pintype "passive"))
      (node (ref "P13") (pin "2") (pinfunction "2_2") (pintype "passive"))
      (node (ref "Q1") (pin "5") (pinfunction "D_5") (pintype "passive"))
      (node (ref "Q1") (pin "6") (pinfunction "D_6") (pintype "passive"))
      (node (ref "Q1") (pin "7") (pinfunction "D_7") (pintype "passive"))
      (node (ref "Q1") (pin "8") (pinfunction "D_8") (pintype "passive"))
      (node (ref "R20") (pin "1") (pinfunction "1_1") (pintype "passive"))
      (node (ref "R21") (pin "1") (pinfunction "1_1") (pintype "passive"))
    )
    (net (code "57") (name "GND") (class "Default")
      (node (ref "*") (pin "2") (pinfunction "GND_2") (pintype "passive"))
      (node (ref "*1") (pin "2") (pinfunction "GND_2") (pintype "passive"))
      (node (ref "C1") (pin "2") (pinfunction "2_2") (pintype "passive"))
      (node (ref "C10") (pin "1") (pinfunction "1_1") (pintype "passive"))
      (node (ref "C11") (pin "1") (pinfunction "1_1") (pintype "passive"))
      (node (ref "C12") (pin "1") (pinfunction "1_1") (pintype "passive"))
      (node (ref "C13") (pin "1") (pinfunction "1_1") (pintype "passive"))
      (node (ref "C16") (pin "1") (pinfunction "1_1") (pintype "passive"))
      (node (ref "C17") (pin "1") (pinfunction "1_1") (pintype "passive"))
      (node (ref "C18") (pin "1") (pinfunction "1_1") (pintype "passive"))
      (node (ref "C19") (pin "2") (pinfunction "2_2") (pintype "passive"))
      (node (ref "C2") (pin "2") (pinfunction "2_2") (pintype "passive"))
      (node (ref "C21") (pin "1") (pinfunction "1_1") (pintype "passive"))
      (node (ref "C22") (pin "1") (pinfunction "1_1") (pintype "passive"))
      (node (ref "C23") (pin "1") (pinfunction "1_1") (pintype "passive"))
      (node (ref "C24") (pin "1") (pinfunction "1_1") (pintype "passive"))
      (node (ref "C27") (pin "1") (pinfunction "1_1") (pintype "passive"))
      (node (ref "C29") (pin "1") (pinfunction "1_1") (pintype "passive"))
      (node (ref "C3") (pin "2") (pinfunction "2_2") (pintype "passive"))
      (node (ref "C30") (pin "1") (pinfunction "1_1") (pintype "passive"))
      (node (ref "C31") (pin "1") (pinfunction "1_1") (pintype "passive"))
      (node (ref "C32") (pin "1") (pinfunction "1_1") (pintype "passive"))
      (node (ref "C33") (pin "1") (pinfunction "1_1") (pintype "passive"))
      (node (ref "C34") (pin "1") (pinfunction "1_1") (pintype "passive"))
      (node (ref "C35") (pin "1") (pinfunction "1_1") (pintype "passive"))
      (node (ref "C36") (pin "1") (pinfunction "1_1") (pintype "passive"))
      (node (ref "C37") (pin "1") (pinfunction "1_1") (pintype "passive"))
      (node (ref "C4") (pin "2") (pinfunction "2_2") (pintype "passive"))
      (node (ref "C45") (pin "1") (pinfunction "1_1") (pintype "passive"))
      (node (ref "C46") (pin "2") (pinfunction "2_2") (pintype "passive"))
      (node (ref "C47") (pin "1") (pinfunction "1_1") (pintype "passive"))
      (node (ref "C5") (pin "1") (pinfunction "1_1") (pintype "passive"))
      (node (ref "C51") (pin "1") (pinfunction "1_1") (pintype "passive"))
      (node (ref "C52") (pin "1") (pinfunction "1_1") (pintype "passive"))
      (node (ref "C53") (pin "2") (pinfunction "2_2") (pintype "passive"))
      (node (ref "C54") (pin "1") (pinfunction "1_1") (pintype "passive"))
      (node (ref "C55") (pin "2") (pinfunction "2_2") (pintype "passive"))
      (node (ref "C6") (pin "1") (pinfunction "1_1") (pintype "passive"))
      (node (ref "C7") (pin "1") (pinfunction "1_1") (pintype "passive"))
      (node (ref "C8") (pin "1") (pinfunction "1_1") (pintype "passive"))
      (node (ref "C9") (pin "1") (pinfunction "1_1") (pintype "passive"))
      (node (ref "CN1") (pin "2") (pinfunction "GND_2") (pintype "passive"))
      (node (ref "D1") (pin "1") (pinfunction "A_1") (pintype "passive"))
      (node (ref "D2") (pin "1") (pinfunction "A_1") (pintype "passive"))
      (node (ref "D3") (pin "2") (pinfunction "K_2") (pintype "passive"))
      (node (ref "D4") (pin "1") (pinfunction "A_1") (pintype "passive"))
      (node (ref "D6") (pin "2") (pinfunction "K_2") (pintype "passive"))
      (node (ref "IC2") (pin "7") (pinfunction "GND_7") (pintype "passive"))
      (node (ref "IC4") (pin "7") (pinfunction "GND_7") (pintype "passive"))
      (node (ref "J2") (pin "4") (pinfunction "4_4") (pintype "passive"))
      (node (ref "MP1584") (pin "1") (pinfunction "IN-_1") (pintype "passive"))
      (node (ref "MP1584") (pin "2") (pinfunction "IN-_2") (pintype "passive"))
      (node (ref "MP1584") (pin "7") (pinfunction "OUT-_7") (pintype "passive"))
      (node (ref "MP1584") (pin "8") (pinfunction "OUT-_8") (pintype "passive"))
      (node (ref "P1") (pin "2") (pinfunction "-_2") (pintype "passive"))
      (node (ref "P10") (pin "4") (pinfunction "GND_4") (pintype "passive"))
      (node (ref "P11") (pin "4") (pinfunction "GND_4") (pintype "passive"))
      (node (ref "P12") (pin "4") (pinfunction "GND_4") (pintype "passive"))
      (node (ref "P13") (pin "1") (pinfunction "1_1") (pintype "passive"))
      (node (ref "P2") (pin "2") (pinfunction "-_2") (pintype "passive"))
      (node (ref "P20") (pin "2") (pinfunction "2_2") (pintype "passive"))
      (node (ref "P3") (pin "25") (pinfunction "C8_25") (pintype "passive"))
      (node (ref "P3") (pin "27") (pinfunction "C6_27") (pintype "passive"))
      (node (ref "P3") (pin "29") (pinfunction "B14_29") (pintype "passive"))
      (node (ref "P5") (pin "1") (pinfunction "GND_1") (pintype "passive"))
      (node (ref "P6") (pin "1") (pinfunction "GND_1") (pintype "passive"))
      (node (ref "P7") (pin "1") (pinfunction "GND_1") (pintype "passive"))
      (node (ref "P8") (pin "1") (pinfunction "GND_1") (pintype "passive"))
      (node (ref "P9") (pin "1") (pinfunction "GND_1") (pintype "passive"))
      (node (ref "Q3") (pin "2") (pinfunction "S_2") (pintype "passive"))
      (node (ref "Q4") (pin "2") (pinfunction "S_2") (pintype "passive"))
      (node (ref "Q5") (pin "2") (pinfunction "S_2") (pintype "passive"))
      (node (ref "Q6") (pin "2") (pinfunction "S_2") (pintype "passive"))
      (node (ref "R18") (pin "1") (pinfunction "1_1") (pintype "passive"))
      (node (ref "R3") (pin "1") (pinfunction "1_1") (pintype "passive"))
      (node (ref "R30") (pin "2") (pinfunction "2_2") (pintype "passive"))
      (node (ref "R31") (pin "2") (pinfunction "2_2") (pintype "passive"))
      (node (ref "R32") (pin "2") (pinfunction "2_2") (pintype "passive"))
      (node (ref "R33") (pin "2") (pinfunction "2_2") (pintype "passive"))
      (node (ref "R4") (pin "2") (pinfunction "2_2") (pintype "passive"))
      (node (ref "R41") (pin "1") (pinfunction "1_1") (pintype "passive"))
      (node (ref "R8") (pin "1") (pinfunction "1_1") (pintype "passive"))
      (node (ref "U2") (pin "18") (pinfunction "GND_2_18") (pintype "passive"))
      (node (ref "U2") (pin "21") (pinfunction "GND_3_21") (pintype "passive"))
      (node (ref "U2") (pin "25") (pinfunction "AGND_25") (pintype "passive"))
      (node (ref "U2") (pin "26") (pinfunction "TEST_26") (pintype "passive"))
      (node (ref "U2") (pin "7") (pinfunction "GND_1_7") (pintype "passive"))
      (node (ref "USB1") (pin "4") (pinfunction "GND_4") (pintype "passive"))
      (node (ref "X3") (pin "2") (pinfunction "GND_2") (pintype "passive"))
      (node (ref "X3") (pin "4") (pinfunction "GND_4") (pintype "passive"))
    )
    (net (code "58") (name "Net-(*-VMotor)") (class "Default")
      (node (ref "*") (pin "1") (pinfunction "VMotor_1") (pintype "passive"))
      (node (ref "C45") (pin "2") (pinfunction "2_2") (pintype "passive"))
      (node (ref "R20") (pin "2") (pinfunction "2_2") (pintype "passive"))
    )
    (net (code "59") (name "Net-(*1-VMotor)") (class "Default")
      (node (ref "*1") (pin "1") (pinfunction "VMotor_1") (pintype "passive"))
      (node (ref "C47") (pin "2") (pinfunction "2_2") (pintype "passive"))
      (node (ref "R21") (pin "2") (pinfunction "2_2") (pintype "passive"))
    )
    (net (code "60") (name "Net-(C27-Pad2)") (class "Default")
      (node (ref "C27") (pin "2") (pinfunction "2_2") (pintype "passive"))
      (node (ref "R7") (pin "1") (pinfunction "1_1") (pintype "passive"))
    )
    (net (code "61") (name "Net-(C37-Pad2)") (class "Default")
      (node (ref "C37") (pin "2") (pinfunction "2_2") (pintype "passive"))
      (node (ref "R17") (pin "1") (pinfunction "1_1") (pintype "passive"))
    )
    (net (code "62") (name "Net-(D2-K)") (class "Default")
      (node (ref "C14") (pin "1") (pinfunction "1_1") (pintype "passive"))
      (node (ref "D2") (pin "2") (pinfunction "K_2") (pintype "passive"))
      (node (ref "IC2") (pin "8") (pinfunction "PH_8") (pintype "passive"))
      (node (ref "L1") (pin "1") (pinfunction "1_1") (pintype "passive"))
    )
    (net (code "63") (name "Net-(D3-A)") (class "Default")
      (node (ref "D3") (pin "1") (pinfunction "A_1") (pintype "passive"))
      (node (ref "R6") (pin "1") (pinfunction "1_1") (pintype "passive"))
    )
    (net (code "64") (name "Net-(D4-K)") (class "Default")
      (node (ref "C28") (pin "1") (pinfunction "1_1") (pintype "passive"))
      (node (ref "D4") (pin "2") (pinfunction "K_2") (pintype "passive"))
      (node (ref "IC4") (pin "8") (pinfunction "PH_8") (pintype "passive"))
      (node (ref "L2") (pin "1") (pinfunction "1_1") (pintype "passive"))
    )
    (net (code "65") (name "Net-(D6-A)") (class "Default")
      (node (ref "D6") (pin "1") (pinfunction "A_1") (pintype "passive"))
      (node (ref "R15") (pin "1") (pinfunction "1_1") (pintype "passive"))
    )
    (net (code "66") (name "Net-(IC2-BOOT)") (class "Default")
      (node (ref "C14") (pin "2") (pinfunction "2_2") (pintype "passive"))
      (node (ref "IC2") (pin "1") (pinfunction "BOOT_1") (pintype "passive"))
    )
    (net (code "67") (name "Net-(IC2-COMP)") (class "Default")
      (node (ref "C24") (pin "2") (pinfunction "2_2") (pintype "passive"))
      (node (ref "IC2") (pin "6") (pinfunction "COMP_6") (pintype "passive"))
      (node (ref "R7") (pin "2") (pinfunction "2_2") (pintype "passive"))
    )
    (net (code "68") (name "Net-(IC2-SS)") (class "Default")
      (node (ref "C23") (pin "2") (pinfunction "2_2") (pintype "passive"))
      (node (ref "IC2") (pin "4") (pinfunction "SS_4") (pintype "passive"))
    )
    (net (code "69") (name "Net-(IC2-VSENSE)") (class "Default")
      (node (ref "IC2") (pin "5") (pinfunction "VSENSE_5") (pintype "passive"))
      (node (ref "R5") (pin "1") (pinfunction "1_1") (pintype "passive"))
      (node (ref "R8") (pin "2") (pinfunction "2_2") (pintype "passive"))
    )
    (net (code "70") (name "Net-(IC4-BOOT)") (class "Default")
      (node (ref "C28") (pin "2") (pinfunction "2_2") (pintype "passive"))
      (node (ref "IC4") (pin "1") (pinfunction "BOOT_1") (pintype "passive"))
    )
    (net (code "71") (name "Net-(IC4-COMP)") (class "Default")
      (node (ref "C36") (pin "2") (pinfunction "2_2") (pintype "passive"))
      (node (ref "IC4") (pin "6") (pinfunction "COMP_6") (pintype "passive"))
      (node (ref "R17") (pin "2") (pinfunction "2_2") (pintype "passive"))
    )
    (net (code "72") (name "Net-(IC4-SS)") (class "Default")
      (node (ref "C35") (pin "2") (pinfunction "2_2") (pintype "passive"))
      (node (ref "IC4") (pin "4") (pinfunction "SS_4") (pintype "passive"))
    )
    (net (code "73") (name "Net-(IC4-VSENSE)") (class "Default")
      (node (ref "IC4") (pin "5") (pinfunction "VSENSE_5") (pintype "passive"))
      (node (ref "R14") (pin "1") (pinfunction "1_1") (pintype "passive"))
      (node (ref "R18") (pin "2") (pinfunction "2_2") (pintype "passive"))
    )
    (net (code "74") (name "Net-(J2-Pad2)") (class "Default")
      (node (ref "J2") (pin "2") (pinfunction "2_2") (pintype "passive"))
      (node (ref "R40") (pin "2") (pinfunction "2_2") (pintype "passive"))
    )
    (net (code "75") (name "Net-(J2-Pad3)") (class "Default")
      (node (ref "J2") (pin "3") (pinfunction "3_3") (pintype "passive"))
      (node (ref "R39") (pin "2") (pinfunction "2_2") (pintype "passive"))
    )
    (net (code "76") (name "Net-(P1-+)") (class "Default")
      (node (ref "P1") (pin "1") (pinfunction "+_1") (pintype "passive"))
      (node (ref "S2") (pin "2") (pinfunction "NO_2") (pintype "passive"))
    )
    (net (code "77") (name "Net-(P15-Pad2)") (class "Default")
      (node (ref "P15") (pin "2") (pinfunction "2_2") (pintype "passive"))
      (node (ref "R22") (pin "1") (pinfunction "1_1") (pintype "passive"))
    )
    (net (code "78") (name "Net-(P16-Pad2)") (class "Default")
      (node (ref "P16") (pin "2") (pinfunction "2_2") (pintype "passive"))
      (node (ref "R23") (pin "1") (pinfunction "1_1") (pintype "passive"))
    )
    (net (code "79") (name "Net-(P17-Pad2)") (class "Default")
      (node (ref "P17") (pin "2") (pinfunction "2_2") (pintype "passive"))
      (node (ref "R24") (pin "1") (pinfunction "1_1") (pintype "passive"))
    )
    (net (code "80") (name "Net-(P18-Pad2)") (class "Default")
      (node (ref "P18") (pin "2") (pinfunction "2_2") (pintype "passive"))
      (node (ref "R25") (pin "1") (pinfunction "1_1") (pintype "passive"))
    )
    (net (code "81") (name "Net-(Q1-G)") (class "Default")
      (node (ref "Q1") (pin "4") (pinfunction "G_4") (pintype "passive"))
      (node (ref "R4") (pin "1") (pinfunction "1_1") (pintype "passive"))
    )
    (net (code "82") (name "Net-(Q3-D)") (class "Default")
      (node (ref "Q3") (pin "3") (pinfunction "D_3") (pintype "passive"))
      (node (ref "R22") (pin "2") (pinfunction "2_2") (pintype "passive"))
    )
    (net (code "83") (name "Net-(Q4-D)") (class "Default")
      (node (ref "Q4") (pin "3") (pinfunction "D_3") (pintype "passive"))
      (node (ref "R23") (pin "2") (pinfunction "2_2") (pintype "passive"))
    )
    (net (code "84") (name "Net-(Q5-D)") (class "Default")
      (node (ref "Q5") (pin "3") (pinfunction "D_3") (pintype "passive"))
      (node (ref "R24") (pin "2") (pinfunction "2_2") (pintype "passive"))
    )
    (net (code "85") (name "Net-(Q6-D)") (class "Default")
      (node (ref "Q6") (pin "3") (pinfunction "D_3") (pintype "passive"))
      (node (ref "R25") (pin "2") (pinfunction "2_2") (pintype "passive"))
    )
    (net (code "86") (name "Net-(R36-Pad2)") (class "Default")
      (node (ref "R36") (pin "2") (pinfunction "2_2") (pintype "passive"))
      (node (ref "R38") (pin "2") (pinfunction "2_2") (pintype "passive"))
    )
    (net (code "87") (name "Net-(S1-COMMON)") (class "Default")
      (node (ref "Q1") (pin "1") (pinfunction "S_1") (pintype "passive"))
      (node (ref "Q1") (pin "2") (pinfunction "S_2") (pintype "passive"))
      (node (ref "Q1") (pin "3") (pinfunction "S_3") (pintype "passive"))
      (node (ref "S1") (pin "1") (pinfunction "COMMON_1") (pintype "passive"))
    )
    (net (code "88") (name "Net-(S1-NO)") (class "Default")
      (node (ref "F1") (pin "2") (pinfunction "2_2") (pintype "passive"))
      (node (ref "S1") (pin "2") (pinfunction "NO_2") (pintype "passive"))
    )
    (net (code "89") (name "Net-(U2-3V3OUT)") (class "Default")
      (node (ref "C54") (pin "2") (pinfunction "2_2") (pintype "passive"))
      (node (ref "U2") (pin "17") (pinfunction "3V3OUT_17") (pintype "passive"))
    )
    (net (code "90") (name "Net-(U2-RESET#)") (class "Default")
      (node (ref "J2") (pin "1") (pinfunction "1_1") (pintype "passive"))
      (node (ref "R38") (pin "1") (pinfunction "1_1") (pintype "passive"))
      (node (ref "R41") (pin "2") (pinfunction "2_2") (pintype "passive"))
      (node (ref "U2") (pin "19") (pinfunction "RESET#_19") (pintype "passive"))
    )
    (net (code "91") (name "Net-(U2-RXD)") (class "Default")
      (node (ref "R37") (pin "2") (pinfunction "2_2") (pintype "passive"))
      (node (ref "U2") (pin "5") (pinfunction "RXD_5") (pintype "passive"))
    )
    (net (code "92") (name "Net-(U2-TXD)") (class "Default")
      (node (ref "R35") (pin "2") (pinfunction "2_2") (pintype "passive"))
      (node (ref "U2") (pin "1") (pinfunction "TXD_1") (pintype "passive"))
    )
    (net (code "93") (name "Net-(U2-USBDM)") (class "Default")
      (node (ref "R39") (pin "1") (pinfunction "1_1") (pintype "passive"))
      (node (ref "U2") (pin "16") (pinfunction "USBDM_16") (pintype "passive"))
    )
    (net (code "94") (name "Net-(U2-USBDP)") (class "Default")
      (node (ref "R40") (pin "1") (pinfunction "1_1") (pintype "passive"))
      (node (ref "U2") (pin "15") (pinfunction "USBDP_15") (pintype "passive"))
    )
    (net (code "95") (name "Net-(U2-VCC)") (class "Default")
      (node (ref "R34") (pin "1") (pinfunction "1_1") (pintype "passive"))
      (node (ref "R36") (pin "1") (pinfunction "1_1") (pintype "passive"))
      (node (ref "U2") (pin "20") (pinfunction "VCC_20") (pintype "passive"))
      (node (ref "U2") (pin "4") (pinfunction "VCCIO_4") (pintype "passive"))
    )
    (net (code "96") (name "RADAR_5V") (class "Default")
      (node (ref "C16") (pin "2") (pinfunction "2_2") (pintype "passive"))
      (node (ref "C17") (pin "2") (pinfunction "2_2") (pintype "passive"))
      (node (ref "C18") (pin "2") (pinfunction "2_2") (pintype "passive"))
      (node (ref "C19") (pin "1") (pinfunction "1_1") (pintype "passive"))
      (node (ref "C31") (pin "2") (pinfunction "2_2") (pintype "passive"))
      (node (ref "C32") (pin "2") (pinfunction "2_2") (pintype "passive"))
      (node (ref "C51") (pin "2") (pinfunction "2_2") (pintype "passive"))
      (node (ref "C52") (pin "2") (pinfunction "2_2") (pintype "passive"))
      (node (ref "CN1") (pin "1") (pinfunction "5V_1") (pintype "passive"))
      (node (ref "L1") (pin "2") (pinfunction "2_2") (pintype "passive"))
      (node (ref "P20") (pin "1") (pinfunction "1_1") (pintype "passive"))
      (node (ref "R15") (pin "2") (pinfunction "2_2") (pintype "passive"))
      (node (ref "R34") (pin "2") (pinfunction "2_2") (pintype "passive"))
      (node (ref "R5") (pin "2") (pinfunction "2_2") (pintype "passive"))
      (node (ref "R6") (pin "2") (pinfunction "2_2") (pintype "passive"))
    )
    (net (code "97") (name "USB_5V") (class "Default")
      (node (ref "C29") (pin "2") (pinfunction "2_2") (pintype "passive"))
      (node (ref "C30") (pin "2") (pinfunction "2_2") (pintype "passive"))
      (node (ref "L2") (pin "2") (pinfunction "2_2") (pintype "passive"))
      (node (ref "R14") (pin "2") (pinfunction "2_2") (pintype "passive"))
      (node (ref "USB1") (pin "1") (pinfunction "VCC_1") (pintype "passive"))
    )
    (net (code "98") (name "VCC 5V") (class "Default")
      (node (ref "C1") (pin "1") (pinfunction "1_1") (pintype "passive"))
      (node (ref "C10") (pin "2") (pinfunction "2_2") (pintype "passive"))
      (node (ref "C11") (pin "2") (pinfunction "2_2") (pintype "passive"))
      (node (ref "C12") (pin "2") (pinfunction "2_2") (pintype "passive"))
      (node (ref "C13") (pin "2") (pinfunction "2_2") (pintype "passive"))
      (node (ref "C2") (pin "1") (pinfunction "1_1") (pintype "passive"))
      (node (ref "C3") (pin "1") (pinfunction "1_1") (pintype "passive"))
      (node (ref "C4") (pin "1") (pinfunction "1_1") (pintype "passive"))
      (node (ref "C6") (pin "2") (pinfunction "2_2") (pintype "passive"))
      (node (ref "C7") (pin "2") (pinfunction "2_2") (pintype "passive"))
      (node (ref "C8") (pin "2") (pinfunction "2_2") (pintype "passive"))
      (node (ref "C9") (pin "2") (pinfunction "2_2") (pintype "passive"))
      (node (ref "MP1584") (pin "5") (pinfunction "OUT+_5") (pintype "passive"))
      (node (ref "MP1584") (pin "6") (pinfunction "OUT+_6") (pintype "passive"))
      (node (ref "P10") (pin "1") (pinfunction "5V_1") (pintype "passive"))
      (node (ref "P11") (pin "1") (pinfunction "5V_1") (pintype "passive"))
      (node (ref "P15") (pin "1") (pinfunction "1_1") (pintype "passive"))
      (node (ref "P16") (pin "1") (pinfunction "1_1") (pintype "passive"))
      (node (ref "P17") (pin "1") (pinfunction "1_1") (pintype "passive"))
      (node (ref "P18") (pin "1") (pinfunction "1_1") (pintype "passive"))
      (node (ref "P3") (pin "1") (pinfunction "5V_1") (pintype "passive"))
      (node (ref "P3") (pin "2") (pinfunction "5V_2") (pintype "passive"))
      (node (ref "P4") (pin "1") (pinfunction "5V_1") (pintype "passive"))
      (node (ref "P4") (pin "2") (pinfunction "5V_2") (pintype "passive"))
      (node (ref "P5") (pin "2") (pinfunction "5V_2") (pintype "passive"))
      (node (ref "P6") (pin "2") (pinfunction "5V_2") (pintype "passive"))
      (node (ref "P7") (pin "2") (pinfunction "5V_2") (pintype "passive"))
      (node (ref "P8") (pin "2") (pinfunction "5V_2") (pintype "passive"))
      (node (ref "P9") (pin "2") (pinfunction "5V_2") (pintype "passive"))
    )
    (net (code "99") (name "VCC 7.4V") (class "Default")
      (node (ref "MP1584") (pin "3") (pinfunction "IN+_3") (pintype "passive"))
      (node (ref "MP1584") (pin "4") (pinfunction "IN+_4") (pintype "passive"))
      (node (ref "R2") (pin "2") (pinfunction "2_2") (pintype "passive"))
      (node (ref "S2") (pin "1") (pinfunction "COMMON_1") (pintype "passive"))
    )
    (net (code "100") (name "VIN") (class "Default")
      (node (ref "D1") (pin "2") (pinfunction "K_2") (pintype "passive"))
      (node (ref "F1") (pin "1") (pinfunction "1_1") (pintype "passive"))
      (node (ref "P2") (pin "1") (pinfunction "+_1") (pintype "passive"))
    )
    (net (code "101") (name "unconnected-(IC2-EN-Pad3)") (class "Default")
      (node (ref "IC2") (pin "3") (pinfunction "EN_3") (pintype "passive"))
    )
    (net (code "102") (name "unconnected-(IC4-EN-Pad3)") (class "Default")
      (node (ref "IC4") (pin "3") (pinfunction "EN_3") (pintype "passive"))
    )
    (net (code "103") (name "unconnected-(J2-PadMH1)") (class "Default")
      (node (ref "J2") (pin "MH1") (pinfunction "MH1_MH1") (pintype "passive"))
    )
    (net (code "104") (name "unconnected-(J2-PadMH2)") (class "Default")
      (node (ref "J2") (pin "MH2") (pinfunction "MH2_MH2") (pintype "passive"))
    )
    (net (code "105") (name "unconnected-(P12-NO-Pad3)") (class "Default")
      (node (ref "P12") (pin "3") (pinfunction "NO_3") (pintype "passive"))
    )
    (net (code "106") (name "unconnected-(P12-NO-Pad8)") (class "Default")
      (node (ref "P12") (pin "8") (pinfunction "NO_8") (pintype "passive"))
    )
    (net (code "107") (name "unconnected-(P12-NO-Pad9)") (class "Default")
      (node (ref "P12") (pin "9") (pinfunction "NO_9") (pintype "passive"))
    )
    (net (code "108") (name "unconnected-(S1-Pad3)") (class "Default")
      (node (ref "S1") (pin "3") (pinfunction "3_3") (pintype "passive"))
    )
    (net (code "109") (name "unconnected-(S2-Pad3)") (class "Default")
      (node (ref "S2") (pin "3") (pinfunction "3_3") (pintype "passive"))
    )
    (net (code "110") (name "unconnected-(U2-CBUS0-Pad23)") (class "Default")
      (node (ref "U2") (pin "23") (pinfunction "CBUS0_23") (pintype "passive"))
    )
    (net (code "111") (name "unconnected-(U2-CBUS1-Pad22)") (class "Default")
      (node (ref "U2") (pin "22") (pinfunction "CBUS1_22") (pintype "passive"))
    )
    (net (code "112") (name "unconnected-(U2-CBUS2-Pad13)") (class "Default")
      (node (ref "U2") (pin "13") (pinfunction "CBUS2_13") (pintype "passive"))
    )
    (net (code "113") (name "unconnected-(U2-CBUS3-Pad14)") (class "Default")
      (node (ref "U2") (pin "14") (pinfunction "CBUS3_14") (pintype "passive"))
    )
    (net (code "114") (name "unconnected-(U2-CBUS4-Pad12)") (class "Default")
      (node (ref "U2") (pin "12") (pinfunction "CBUS4_12") (pintype "passive"))
    )
    (net (code "115") (name "unconnected-(U2-CTS#-Pad11)") (class "Default")
      (node (ref "U2") (pin "11") (pinfunction "CTS#_11") (pintype "passive"))
    )
    (net (code "116") (name "unconnected-(U2-DCD#-Pad10)") (class "Default")
      (node (ref "U2") (pin "10") (pinfunction "DCD#_10") (pintype "passive"))
    )
    (net (code "117") (name "unconnected-(U2-DSR#-Pad9)") (class "Default")
      (node (ref "U2") (pin "9") (pinfunction "DSR#_9") (pintype "passive"))
    )
    (net (code "118") (name "unconnected-(U2-DTR#-Pad2)") (class "Default")
      (node (ref "U2") (pin "2") (pinfunction "DTR#_2") (pintype "passive"))
    )
    (net (code "119") (name "unconnected-(U2-NC_1-Pad8)") (class "Default")
      (node (ref "U2") (pin "8") (pinfunction "NC_1_8") (pintype "passive"))
    )
    (net (code "120") (name "unconnected-(U2-NC_2-Pad24)") (class "Default")
      (node (ref "U2") (pin "24") (pinfunction "NC_2_24") (pintype "passive"))
    )
    (net (code "121") (name "unconnected-(U2-RI#-Pad6)") (class "Default")
      (node (ref "U2") (pin "6") (pinfunction "RI#_6") (pintype "passive"))
    )
    (net (code "122") (name "unconnected-(U2-RTS#-Pad3)") (class "Default")
      (node (ref "U2") (pin "3") (pinfunction "RTS#_3") (pintype "passive"))
    )
    (net (code "123") (name "unconnected-(USB1-D+-Pad3)") (class "Default")
      (node (ref "USB1") (pin "3") (pinfunction "D+_3") (pintype "passive"))
    )
    (net (code "124") (name "unconnected-(USB1-D--Pad2)") (class "Default")
      (node (ref "USB1") (pin "2") (pinfunction "D-_2") (pintype "passive"))
    )
    (net (code "125") (name "unconnected-(USB1-SH1-Pad5)") (class "Default")
      (node (ref "USB1") (pin "5") (pinfunction "SH1_5") (pintype "passive"))
    )
    (net (code "126") (name "unconnected-(USB1-SH2-Pad6)") (class "Default")
      (node (ref "USB1") (pin "6") (pinfunction "SH2_6") (pintype "passive"))
    )
  )
)
